# sqrwear-ledmatrix.net
KiCad netlist of a schematic drawn in EAGLE
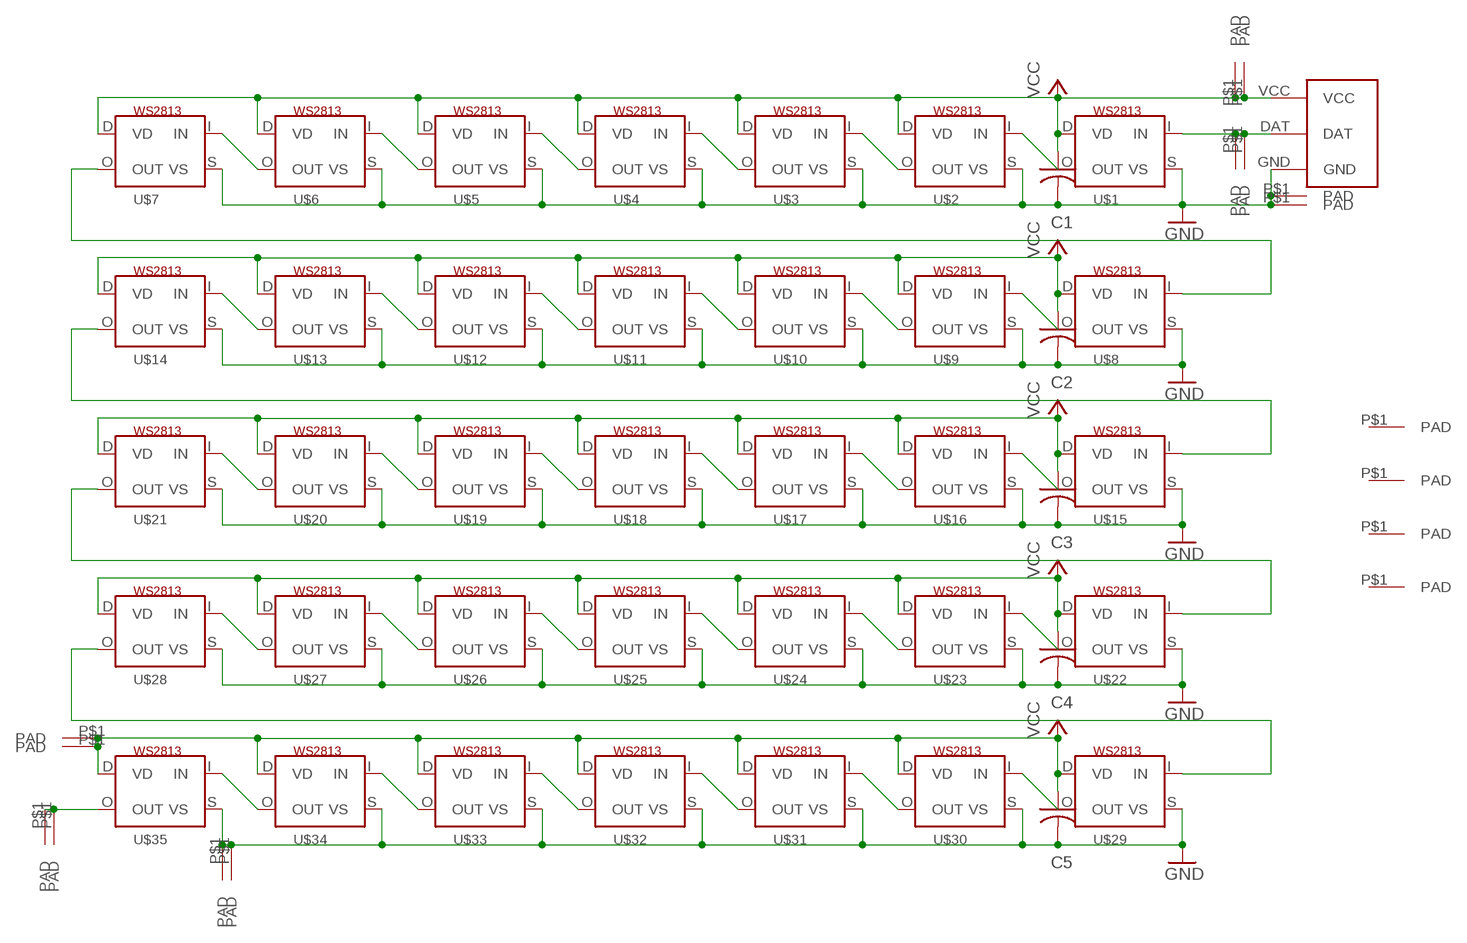
[diagram p0: schematic, sheet 1]

(export (version "E")
  (design (tool "Eeschema 10.0.6"))
  (components
    (comp (ref "C1")
      (value "C-USC0805K")
      (footprint "eagle-import:C0805K")
      (libsource (lib "eagle-import") (part "C-USC0805K"))
    )
    (comp (ref "C2")
      (value "C-USC0805K")
      (footprint "eagle-import:C0805K")
      (libsource (lib "eagle-import") (part "C-USC0805K"))
    )
    (comp (ref "C3")
      (value "C-USC0805K")
      (footprint "eagle-import:C0805K")
      (libsource (lib "eagle-import") (part "C-USC0805K"))
    )
    (comp (ref "C4")
      (value "C-USC0805K")
      (footprint "eagle-import:C0805K")
      (libsource (lib "eagle-import") (part "C-USC0805K"))
    )
    (comp (ref "C5")
      (value "C-USC0805K")
      (footprint "eagle-import:C0805K")
      (libsource (lib "eagle-import") (part "C-USC0805K"))
    )
    (comp (ref "U$1")
      (value "WS2813")
      (footprint "eagle-import:RGBLED5050_4")
      (libsource (lib "eagle-import") (part "WS2813"))
    )
    (comp (ref "U$2")
      (value "WS2813")
      (footprint "eagle-import:RGBLED5050_4")
      (libsource (lib "eagle-import") (part "WS2813"))
    )
    (comp (ref "U$3")
      (value "WS2813")
      (footprint "eagle-import:RGBLED5050_4")
      (libsource (lib "eagle-import") (part "WS2813"))
    )
    (comp (ref "U$4")
      (value "WS2813")
      (footprint "eagle-import:RGBLED5050_4")
      (libsource (lib "eagle-import") (part "WS2813"))
    )
    (comp (ref "U$5")
      (value "WS2813")
      (footprint "eagle-import:RGBLED5050_4")
      (libsource (lib "eagle-import") (part "WS2813"))
    )
    (comp (ref "U$6")
      (value "WS2813")
      (footprint "eagle-import:RGBLED5050_4")
      (libsource (lib "eagle-import") (part "WS2813"))
    )
    (comp (ref "U$7")
      (value "WS2813")
      (footprint "eagle-import:RGBLED5050_4")
      (libsource (lib "eagle-import") (part "WS2813"))
    )
    (comp (ref "U$8")
      (value "WS2813")
      (footprint "eagle-import:RGBLED5050_4")
      (libsource (lib "eagle-import") (part "WS2813"))
    )
    (comp (ref "U$9")
      (value "WS2813")
      (footprint "eagle-import:RGBLED5050_4")
      (libsource (lib "eagle-import") (part "WS2813"))
    )
    (comp (ref "U$10")
      (value "WS2813")
      (footprint "eagle-import:RGBLED5050_4")
      (libsource (lib "eagle-import") (part "WS2813"))
    )
    (comp (ref "U$11")
      (value "WS2813")
      (footprint "eagle-import:RGBLED5050_4")
      (libsource (lib "eagle-import") (part "WS2813"))
    )
    (comp (ref "U$12")
      (value "WS2813")
      (footprint "eagle-import:RGBLED5050_4")
      (libsource (lib "eagle-import") (part "WS2813"))
    )
    (comp (ref "U$13")
      (value "WS2813")
      (footprint "eagle-import:RGBLED5050_4")
      (libsource (lib "eagle-import") (part "WS2813"))
    )
    (comp (ref "U$14")
      (value "WS2813")
      (footprint "eagle-import:RGBLED5050_4")
      (libsource (lib "eagle-import") (part "WS2813"))
    )
    (comp (ref "U$15")
      (value "WS2813")
      (footprint "eagle-import:RGBLED5050_4")
      (libsource (lib "eagle-import") (part "WS2813"))
    )
    (comp (ref "U$16")
      (value "WS2813")
      (footprint "eagle-import:RGBLED5050_4")
      (libsource (lib "eagle-import") (part "WS2813"))
    )
    (comp (ref "U$17")
      (value "WS2813")
      (footprint "eagle-import:RGBLED5050_4")
      (libsource (lib "eagle-import") (part "WS2813"))
    )
    (comp (ref "U$18")
      (value "WS2813")
      (footprint "eagle-import:RGBLED5050_4")
      (libsource (lib "eagle-import") (part "WS2813"))
    )
    (comp (ref "U$19")
      (value "WS2813")
      (footprint "eagle-import:RGBLED5050_4")
      (libsource (lib "eagle-import") (part "WS2813"))
    )
    (comp (ref "U$20")
      (value "WS2813")
      (footprint "eagle-import:RGBLED5050_4")
      (libsource (lib "eagle-import") (part "WS2813"))
    )
    (comp (ref "U$21")
      (value "WS2813")
      (footprint "eagle-import:RGBLED5050_4")
      (libsource (lib "eagle-import") (part "WS2813"))
    )
    (comp (ref "U$22")
      (value "WS2813")
      (footprint "eagle-import:RGBLED5050_4")
      (libsource (lib "eagle-import") (part "WS2813"))
    )
    (comp (ref "U$23")
      (value "WS2813")
      (footprint "eagle-import:RGBLED5050_4")
      (libsource (lib "eagle-import") (part "WS2813"))
    )
    (comp (ref "U$24")
      (value "WS2813")
      (footprint "eagle-import:RGBLED5050_4")
      (libsource (lib "eagle-import") (part "WS2813"))
    )
    (comp (ref "U$25")
      (value "WS2813")
      (footprint "eagle-import:RGBLED5050_4")
      (libsource (lib "eagle-import") (part "WS2813"))
    )
    (comp (ref "U$26")
      (value "WS2813")
      (footprint "eagle-import:RGBLED5050_4")
      (libsource (lib "eagle-import") (part "WS2813"))
    )
    (comp (ref "U$27")
      (value "WS2813")
      (footprint "eagle-import:RGBLED5050_4")
      (libsource (lib "eagle-import") (part "WS2813"))
    )
    (comp (ref "U$28")
      (value "WS2813")
      (footprint "eagle-import:RGBLED5050_4")
      (libsource (lib "eagle-import") (part "WS2813"))
    )
    (comp (ref "U$29")
      (value "WS2813")
      (footprint "eagle-import:RGBLED5050_4")
      (libsource (lib "eagle-import") (part "WS2813"))
    )
    (comp (ref "U$30")
      (value "WS2813")
      (footprint "eagle-import:RGBLED5050_4")
      (libsource (lib "eagle-import") (part "WS2813"))
    )
    (comp (ref "U$31")
      (value "WS2813")
      (footprint "eagle-import:RGBLED5050_4")
      (libsource (lib "eagle-import") (part "WS2813"))
    )
    (comp (ref "U$32")
      (value "WS2813")
      (footprint "eagle-import:RGBLED5050_4")
      (libsource (lib "eagle-import") (part "WS2813"))
    )
    (comp (ref "U$33")
      (value "WS2813")
      (footprint "eagle-import:RGBLED5050_4")
      (libsource (lib "eagle-import") (part "WS2813"))
    )
    (comp (ref "U$34")
      (value "WS2813")
      (footprint "eagle-import:RGBLED5050_4")
      (libsource (lib "eagle-import") (part "WS2813"))
    )
    (comp (ref "U$35")
      (value "WS2813")
      (footprint "eagle-import:RGBLED5050_4")
      (libsource (lib "eagle-import") (part "WS2813"))
    )
    (comp (ref "U$36")
      (value "SQWMINI-MATRIX")
      (footprint "eagle-import:SQWMINI-MATRIX")
      (libsource (lib "eagle-import") (part "SQWMINI-MATRIX"))
    )
    (comp (ref "U$37")
      (value "TESTPAD")
      (footprint "eagle-import:TESTPAD")
      (libsource (lib "eagle-import") (part "TESTPAD"))
    )
    (comp (ref "U$38")
      (value "TESTPAD")
      (footprint "eagle-import:TESTPAD")
      (libsource (lib "eagle-import") (part "TESTPAD"))
    )
    (comp (ref "U$39")
      (value "TESTPAD")
      (footprint "eagle-import:TESTPAD")
      (libsource (lib "eagle-import") (part "TESTPAD"))
    )
    (comp (ref "U$40")
      (value "TESTPAD")
      (footprint "eagle-import:TESTPAD")
      (libsource (lib "eagle-import") (part "TESTPAD"))
    )
    (comp (ref "U$41")
      (value "TESTPAD")
      (footprint "eagle-import:TESTPAD")
      (libsource (lib "eagle-import") (part "TESTPAD"))
    )
    (comp (ref "U$42")
      (value "TESTPAD")
      (footprint "eagle-import:TESTPAD")
      (libsource (lib "eagle-import") (part "TESTPAD"))
    )
    (comp (ref "U$43")
      (value "TESTPAD")
      (footprint "eagle-import:TESTPAD")
      (libsource (lib "eagle-import") (part "TESTPAD"))
    )
    (comp (ref "U$44")
      (value "TESTPAD")
      (footprint "eagle-import:TESTPAD")
      (libsource (lib "eagle-import") (part "TESTPAD"))
    )
    (comp (ref "U$45")
      (value "TESTPAD")
      (footprint "eagle-import:TESTPAD")
      (libsource (lib "eagle-import") (part "TESTPAD"))
    )
    (comp (ref "U$46")
      (value "TESTPAD")
      (footprint "eagle-import:TESTPAD")
      (libsource (lib "eagle-import") (part "TESTPAD"))
    )
    (comp (ref "U$47")
      (value "TESTPAD")
      (footprint "eagle-import:TESTPAD")
      (libsource (lib "eagle-import") (part "TESTPAD"))
    )
    (comp (ref "U$48")
      (value "TESTPAD")
      (footprint "eagle-import:TESTPAD")
      (libsource (lib "eagle-import") (part "TESTPAD"))
    )
    (comp (ref "U$49")
      (value "TESTPAD")
      (footprint "eagle-import:TESTPAD")
      (libsource (lib "eagle-import") (part "TESTPAD"))
    )
    (comp (ref "U$50")
      (value "TESTPAD")
      (footprint "eagle-import:TESTPAD")
      (libsource (lib "eagle-import") (part "TESTPAD"))
    )
    (comp (ref "U$51")
      (value "TESTPAD")
      (footprint "eagle-import:TESTPAD")
      (libsource (lib "eagle-import") (part "TESTPAD"))
    )
    (comp (ref "U$52")
      (value "TESTPAD")
      (footprint "eagle-import:TESTPAD")
      (libsource (lib "eagle-import") (part "TESTPAD"))
    )
  )
  (nets
    (net (code "1") (name "GND") (class "Default")
      (node (ref "C1") (pin "2") (pinfunction "2_2") (pintype "passive"))
      (node (ref "C2") (pin "2") (pinfunction "2_2") (pintype "passive"))
      (node (ref "C3") (pin "2") (pinfunction "2_2") (pintype "passive"))
      (node (ref "C4") (pin "2") (pinfunction "2_2") (pintype "passive"))
      (node (ref "C5") (pin "2") (pinfunction "2_2") (pintype "passive"))
      (node (ref "U$1") (pin "S") (pinfunction "VS_S") (pintype "power_in"))
      (node (ref "U$10") (pin "S") (pinfunction "VS_S") (pintype "power_in"))
      (node (ref "U$11") (pin "S") (pinfunction "VS_S") (pintype "power_in"))
      (node (ref "U$12") (pin "S") (pinfunction "VS_S") (pintype "power_in"))
      (node (ref "U$13") (pin "S") (pinfunction "VS_S") (pintype "power_in"))
      (node (ref "U$14") (pin "S") (pinfunction "VS_S") (pintype "power_in"))
      (node (ref "U$15") (pin "S") (pinfunction "VS_S") (pintype "power_in"))
      (node (ref "U$16") (pin "S") (pinfunction "VS_S") (pintype "power_in"))
      (node (ref "U$17") (pin "S") (pinfunction "VS_S") (pintype "power_in"))
      (node (ref "U$18") (pin "S") (pinfunction "VS_S") (pintype "power_in"))
      (node (ref "U$19") (pin "S") (pinfunction "VS_S") (pintype "power_in"))
      (node (ref "U$2") (pin "S") (pinfunction "VS_S") (pintype "power_in"))
      (node (ref "U$20") (pin "S") (pinfunction "VS_S") (pintype "power_in"))
      (node (ref "U$21") (pin "S") (pinfunction "VS_S") (pintype "power_in"))
      (node (ref "U$22") (pin "S") (pinfunction "VS_S") (pintype "power_in"))
      (node (ref "U$23") (pin "S") (pinfunction "VS_S") (pintype "power_in"))
      (node (ref "U$24") (pin "S") (pinfunction "VS_S") (pintype "power_in"))
      (node (ref "U$25") (pin "S") (pinfunction "VS_S") (pintype "power_in"))
      (node (ref "U$26") (pin "S") (pinfunction "VS_S") (pintype "power_in"))
      (node (ref "U$27") (pin "S") (pinfunction "VS_S") (pintype "power_in"))
      (node (ref "U$28") (pin "S") (pinfunction "VS_S") (pintype "power_in"))
      (node (ref "U$29") (pin "S") (pinfunction "VS_S") (pintype "power_in"))
      (node (ref "U$3") (pin "S") (pinfunction "VS_S") (pintype "power_in"))
      (node (ref "U$30") (pin "S") (pinfunction "VS_S") (pintype "power_in"))
      (node (ref "U$31") (pin "S") (pinfunction "VS_S") (pintype "power_in"))
      (node (ref "U$32") (pin "S") (pinfunction "VS_S") (pintype "power_in"))
      (node (ref "U$33") (pin "S") (pinfunction "VS_S") (pintype "power_in"))
      (node (ref "U$34") (pin "S") (pinfunction "VS_S") (pintype "power_in"))
      (node (ref "U$35") (pin "S") (pinfunction "VS_S") (pintype "power_in"))
      (node (ref "U$36") (pin "GND") (pinfunction "GND_GND") (pintype "bidirectional"))
      (node (ref "U$39") (pin "P$1") (pinfunction "PAD_P$1") (pintype "bidirectional"))
      (node (ref "U$4") (pin "S") (pinfunction "VS_S") (pintype "power_in"))
      (node (ref "U$40") (pin "P$1") (pinfunction "PAD_P$1") (pintype "bidirectional"))
      (node (ref "U$45") (pin "P$1") (pinfunction "PAD_P$1") (pintype "bidirectional"))
      (node (ref "U$46") (pin "P$1") (pinfunction "PAD_P$1") (pintype "bidirectional"))
      (node (ref "U$5") (pin "S") (pinfunction "VS_S") (pintype "power_in"))
      (node (ref "U$6") (pin "S") (pinfunction "VS_S") (pintype "power_in"))
      (node (ref "U$7") (pin "S") (pinfunction "VS_S") (pintype "power_in"))
      (node (ref "U$8") (pin "S") (pinfunction "VS_S") (pintype "power_in"))
      (node (ref "U$9") (pin "S") (pinfunction "VS_S") (pintype "power_in"))
    )
    (net (code "2") (name "Net-(U$1-IN)") (class "Default")
      (node (ref "U$1") (pin "I") (pinfunction "IN_I") (pintype "input"))
      (node (ref "U$36") (pin "DAT") (pinfunction "DAT_DAT") (pintype "bidirectional"))
      (node (ref "U$41") (pin "P$1") (pinfunction "PAD_P$1") (pintype "bidirectional"))
      (node (ref "U$42") (pin "P$1") (pinfunction "PAD_P$1") (pintype "bidirectional"))
    )
    (net (code "3") (name "Net-(U$1-OUT)") (class "Default")
      (node (ref "U$1") (pin "O") (pinfunction "OUT_O") (pintype "output"))
      (node (ref "U$2") (pin "I") (pinfunction "IN_I") (pintype "input"))
    )
    (net (code "4") (name "Net-(U$2-OUT)") (class "Default")
      (node (ref "U$2") (pin "O") (pinfunction "OUT_O") (pintype "output"))
      (node (ref "U$3") (pin "I") (pinfunction "IN_I") (pintype "input"))
    )
    (net (code "5") (name "Net-(U$3-OUT)") (class "Default")
      (node (ref "U$3") (pin "O") (pinfunction "OUT_O") (pintype "output"))
      (node (ref "U$4") (pin "I") (pinfunction "IN_I") (pintype "input"))
    )
    (net (code "6") (name "Net-(U$4-OUT)") (class "Default")
      (node (ref "U$4") (pin "O") (pinfunction "OUT_O") (pintype "output"))
      (node (ref "U$5") (pin "I") (pinfunction "IN_I") (pintype "input"))
    )
    (net (code "7") (name "Net-(U$5-OUT)") (class "Default")
      (node (ref "U$5") (pin "O") (pinfunction "OUT_O") (pintype "output"))
      (node (ref "U$6") (pin "I") (pinfunction "IN_I") (pintype "input"))
    )
    (net (code "8") (name "Net-(U$6-OUT)") (class "Default")
      (node (ref "U$6") (pin "O") (pinfunction "OUT_O") (pintype "output"))
      (node (ref "U$7") (pin "I") (pinfunction "IN_I") (pintype "input"))
    )
    (net (code "9") (name "Net-(U$7-OUT)") (class "Default")
      (node (ref "U$7") (pin "O") (pinfunction "OUT_O") (pintype "output"))
      (node (ref "U$8") (pin "I") (pinfunction "IN_I") (pintype "input"))
    )
    (net (code "10") (name "Net-(U$8-OUT)") (class "Default")
      (node (ref "U$8") (pin "O") (pinfunction "OUT_O") (pintype "output"))
      (node (ref "U$9") (pin "I") (pinfunction "IN_I") (pintype "input"))
    )
    (net (code "11") (name "Net-(U$10-IN)") (class "Default")
      (node (ref "U$10") (pin "I") (pinfunction "IN_I") (pintype "input"))
      (node (ref "U$9") (pin "O") (pinfunction "OUT_O") (pintype "output"))
    )
    (net (code "12") (name "Net-(U$10-OUT)") (class "Default")
      (node (ref "U$10") (pin "O") (pinfunction "OUT_O") (pintype "output"))
      (node (ref "U$11") (pin "I") (pinfunction "IN_I") (pintype "input"))
    )
    (net (code "13") (name "Net-(U$11-OUT)") (class "Default")
      (node (ref "U$11") (pin "O") (pinfunction "OUT_O") (pintype "output"))
      (node (ref "U$12") (pin "I") (pinfunction "IN_I") (pintype "input"))
    )
    (net (code "14") (name "Net-(U$12-OUT)") (class "Default")
      (node (ref "U$12") (pin "O") (pinfunction "OUT_O") (pintype "output"))
      (node (ref "U$13") (pin "I") (pinfunction "IN_I") (pintype "input"))
    )
    (net (code "15") (name "Net-(U$13-OUT)") (class "Default")
      (node (ref "U$13") (pin "O") (pinfunction "OUT_O") (pintype "output"))
      (node (ref "U$14") (pin "I") (pinfunction "IN_I") (pintype "input"))
    )
    (net (code "16") (name "Net-(U$14-OUT)") (class "Default")
      (node (ref "U$14") (pin "O") (pinfunction "OUT_O") (pintype "output"))
      (node (ref "U$15") (pin "I") (pinfunction "IN_I") (pintype "input"))
    )
    (net (code "17") (name "Net-(U$15-OUT)") (class "Default")
      (node (ref "U$15") (pin "O") (pinfunction "OUT_O") (pintype "output"))
      (node (ref "U$16") (pin "I") (pinfunction "IN_I") (pintype "input"))
    )
    (net (code "18") (name "Net-(U$16-OUT)") (class "Default")
      (node (ref "U$16") (pin "O") (pinfunction "OUT_O") (pintype "output"))
      (node (ref "U$17") (pin "I") (pinfunction "IN_I") (pintype "input"))
    )
    (net (code "19") (name "Net-(U$17-OUT)") (class "Default")
      (node (ref "U$17") (pin "O") (pinfunction "OUT_O") (pintype "output"))
      (node (ref "U$18") (pin "I") (pinfunction "IN_I") (pintype "input"))
    )
    (net (code "20") (name "Net-(U$18-OUT)") (class "Default")
      (node (ref "U$18") (pin "O") (pinfunction "OUT_O") (pintype "output"))
      (node (ref "U$19") (pin "I") (pinfunction "IN_I") (pintype "input"))
    )
    (net (code "21") (name "Net-(U$19-OUT)") (class "Default")
      (node (ref "U$19") (pin "O") (pinfunction "OUT_O") (pintype "output"))
      (node (ref "U$20") (pin "I") (pinfunction "IN_I") (pintype "input"))
    )
    (net (code "22") (name "Net-(U$20-OUT)") (class "Default")
      (node (ref "U$20") (pin "O") (pinfunction "OUT_O") (pintype "output"))
      (node (ref "U$21") (pin "I") (pinfunction "IN_I") (pintype "input"))
    )
    (net (code "23") (name "Net-(U$21-OUT)") (class "Default")
      (node (ref "U$21") (pin "O") (pinfunction "OUT_O") (pintype "output"))
      (node (ref "U$22") (pin "I") (pinfunction "IN_I") (pintype "input"))
    )
    (net (code "24") (name "Net-(U$22-OUT)") (class "Default")
      (node (ref "U$22") (pin "O") (pinfunction "OUT_O") (pintype "output"))
      (node (ref "U$23") (pin "I") (pinfunction "IN_I") (pintype "input"))
    )
    (net (code "25") (name "Net-(U$23-OUT)") (class "Default")
      (node (ref "U$23") (pin "O") (pinfunction "OUT_O") (pintype "output"))
      (node (ref "U$24") (pin "I") (pinfunction "IN_I") (pintype "input"))
    )
    (net (code "26") (name "Net-(U$24-OUT)") (class "Default")
      (node (ref "U$24") (pin "O") (pinfunction "OUT_O") (pintype "output"))
      (node (ref "U$25") (pin "I") (pinfunction "IN_I") (pintype "input"))
    )
    (net (code "27") (name "Net-(U$25-OUT)") (class "Default")
      (node (ref "U$25") (pin "O") (pinfunction "OUT_O") (pintype "output"))
      (node (ref "U$26") (pin "I") (pinfunction "IN_I") (pintype "input"))
    )
    (net (code "28") (name "Net-(U$26-OUT)") (class "Default")
      (node (ref "U$26") (pin "O") (pinfunction "OUT_O") (pintype "output"))
      (node (ref "U$27") (pin "I") (pinfunction "IN_I") (pintype "input"))
    )
    (net (code "29") (name "Net-(U$27-OUT)") (class "Default")
      (node (ref "U$27") (pin "O") (pinfunction "OUT_O") (pintype "output"))
      (node (ref "U$28") (pin "I") (pinfunction "IN_I") (pintype "input"))
    )
    (net (code "30") (name "Net-(U$28-OUT)") (class "Default")
      (node (ref "U$28") (pin "O") (pinfunction "OUT_O") (pintype "output"))
      (node (ref "U$29") (pin "I") (pinfunction "IN_I") (pintype "input"))
    )
    (net (code "31") (name "Net-(U$29-OUT)") (class "Default")
      (node (ref "U$29") (pin "O") (pinfunction "OUT_O") (pintype "output"))
      (node (ref "U$30") (pin "I") (pinfunction "IN_I") (pintype "input"))
    )
    (net (code "32") (name "Net-(U$30-OUT)") (class "Default")
      (node (ref "U$30") (pin "O") (pinfunction "OUT_O") (pintype "output"))
      (node (ref "U$31") (pin "I") (pinfunction "IN_I") (pintype "input"))
    )
    (net (code "33") (name "Net-(U$31-OUT)") (class "Default")
      (node (ref "U$31") (pin "O") (pinfunction "OUT_O") (pintype "output"))
      (node (ref "U$32") (pin "I") (pinfunction "IN_I") (pintype "input"))
    )
    (net (code "34") (name "Net-(U$32-OUT)") (class "Default")
      (node (ref "U$32") (pin "O") (pinfunction "OUT_O") (pintype "output"))
      (node (ref "U$33") (pin "I") (pinfunction "IN_I") (pintype "input"))
    )
    (net (code "35") (name "Net-(U$33-OUT)") (class "Default")
      (node (ref "U$33") (pin "O") (pinfunction "OUT_O") (pintype "output"))
      (node (ref "U$34") (pin "I") (pinfunction "IN_I") (pintype "input"))
    )
    (net (code "36") (name "Net-(U$34-OUT)") (class "Default")
      (node (ref "U$34") (pin "O") (pinfunction "OUT_O") (pintype "output"))
      (node (ref "U$35") (pin "I") (pinfunction "IN_I") (pintype "input"))
    )
    (net (code "37") (name "Net-(U$35-OUT)") (class "Default")
      (node (ref "U$35") (pin "O") (pinfunction "OUT_O") (pintype "output"))
      (node (ref "U$47") (pin "P$1") (pinfunction "PAD_P$1") (pintype "bidirectional"))
      (node (ref "U$48") (pin "P$1") (pinfunction "PAD_P$1") (pintype "bidirectional"))
    )
    (net (code "38") (name "VCC") (class "Default")
      (node (ref "C1") (pin "1") (pinfunction "1_1") (pintype "passive"))
      (node (ref "C2") (pin "1") (pinfunction "1_1") (pintype "passive"))
      (node (ref "C3") (pin "1") (pinfunction "1_1") (pintype "passive"))
      (node (ref "C4") (pin "1") (pinfunction "1_1") (pintype "passive"))
      (node (ref "C5") (pin "1") (pinfunction "1_1") (pintype "passive"))
      (node (ref "U$1") (pin "D") (pinfunction "VD_D") (pintype "power_in"))
      (node (ref "U$10") (pin "D") (pinfunction "VD_D") (pintype "power_in"))
      (node (ref "U$11") (pin "D") (pinfunction "VD_D") (pintype "power_in"))
      (node (ref "U$12") (pin "D") (pinfunction "VD_D") (pintype "power_in"))
      (node (ref "U$13") (pin "D") (pinfunction "VD_D") (pintype "power_in"))
      (node (ref "U$14") (pin "D") (pinfunction "VD_D") (pintype "power_in"))
      (node (ref "U$15") (pin "D") (pinfunction "VD_D") (pintype "power_in"))
      (node (ref "U$16") (pin "D") (pinfunction "VD_D") (pintype "power_in"))
      (node (ref "U$17") (pin "D") (pinfunction "VD_D") (pintype "power_in"))
      (node (ref "U$18") (pin "D") (pinfunction "VD_D") (pintype "power_in"))
      (node (ref "U$19") (pin "D") (pinfunction "VD_D") (pintype "power_in"))
      (node (ref "U$2") (pin "D") (pinfunction "VD_D") (pintype "power_in"))
      (node (ref "U$20") (pin "D") (pinfunction "VD_D") (pintype "power_in"))
      (node (ref "U$21") (pin "D") (pinfunction "VD_D") (pintype "power_in"))
      (node (ref "U$22") (pin "D") (pinfunction "VD_D") (pintype "power_in"))
      (node (ref "U$23") (pin "D") (pinfunction "VD_D") (pintype "power_in"))
      (node (ref "U$24") (pin "D") (pinfunction "VD_D") (pintype "power_in"))
      (node (ref "U$25") (pin "D") (pinfunction "VD_D") (pintype "power_in"))
      (node (ref "U$26") (pin "D") (pinfunction "VD_D") (pintype "power_in"))
      (node (ref "U$27") (pin "D") (pinfunction "VD_D") (pintype "power_in"))
      (node (ref "U$28") (pin "D") (pinfunction "VD_D") (pintype "power_in"))
      (node (ref "U$29") (pin "D") (pinfunction "VD_D") (pintype "power_in"))
      (node (ref "U$3") (pin "D") (pinfunction "VD_D") (pintype "power_in"))
      (node (ref "U$30") (pin "D") (pinfunction "VD_D") (pintype "power_in"))
      (node (ref "U$31") (pin "D") (pinfunction "VD_D") (pintype "power_in"))
      (node (ref "U$32") (pin "D") (pinfunction "VD_D") (pintype "power_in"))
      (node (ref "U$33") (pin "D") (pinfunction "VD_D") (pintype "power_in"))
      (node (ref "U$34") (pin "D") (pinfunction "VD_D") (pintype "power_in"))
      (node (ref "U$35") (pin "D") (pinfunction "VD_D") (pintype "power_in"))
      (node (ref "U$36") (pin "VCC") (pinfunction "VCC_VCC") (pintype "bidirectional"))
      (node (ref "U$37") (pin "P$1") (pinfunction "PAD_P$1") (pintype "bidirectional"))
      (node (ref "U$38") (pin "P$1") (pinfunction "PAD_P$1") (pintype "bidirectional"))
      (node (ref "U$4") (pin "D") (pinfunction "VD_D") (pintype "power_in"))
      (node (ref "U$43") (pin "P$1") (pinfunction "PAD_P$1") (pintype "bidirectional"))
      (node (ref "U$44") (pin "P$1") (pinfunction "PAD_P$1") (pintype "bidirectional"))
      (node (ref "U$5") (pin "D") (pinfunction "VD_D") (pintype "power_in"))
      (node (ref "U$6") (pin "D") (pinfunction "VD_D") (pintype "power_in"))
      (node (ref "U$7") (pin "D") (pinfunction "VD_D") (pintype "power_in"))
      (node (ref "U$8") (pin "D") (pinfunction "VD_D") (pintype "power_in"))
      (node (ref "U$9") (pin "D") (pinfunction "VD_D") (pintype "power_in"))
    )
    (net (code "39") (name "unconnected-(U$49-PAD-PadP$1)") (class "Default")
      (node (ref "U$49") (pin "P$1") (pinfunction "PAD_P$1") (pintype "bidirectional"))
    )
    (net (code "40") (name "unconnected-(U$50-PAD-PadP$1)") (class "Default")
      (node (ref "U$50") (pin "P$1") (pinfunction "PAD_P$1") (pintype "bidirectional"))
    )
    (net (code "41") (name "unconnected-(U$51-PAD-PadP$1)") (class "Default")
      (node (ref "U$51") (pin "P$1") (pinfunction "PAD_P$1") (pintype "bidirectional"))
    )
    (net (code "42") (name "unconnected-(U$52-PAD-PadP$1)") (class "Default")
      (node (ref "U$52") (pin "P$1") (pinfunction "PAD_P$1") (pintype "bidirectional"))
    )
  )
)
